# micro-circuit-ATMEGA32M1.net
KiCad netlist of a schematic drawn in Altium Designer
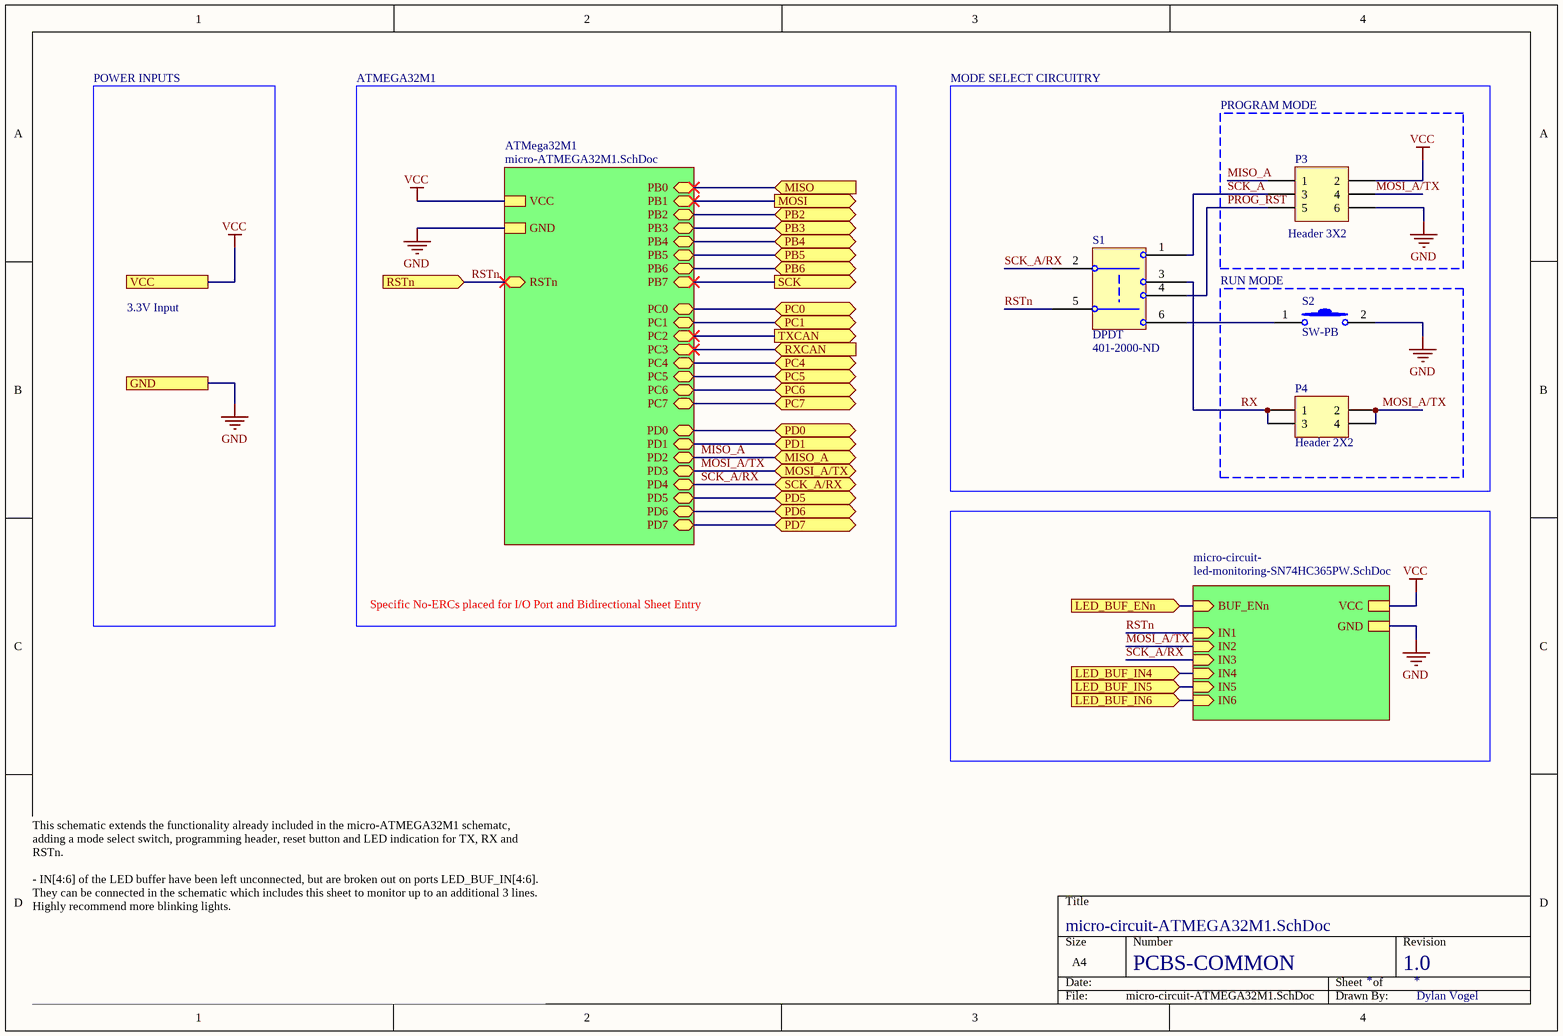
[diagram p0: micro-circuit-ATMEGA32M1.SchDoc]

(export (version "E")
  (design (tool "Eeschema 10.0.6"))
  (components
    (comp (ref "P3")
      (value "Header 3X2")
      (footprint "HDR2X3")
      (description "Header, 3-Pin, Dual row. Programming header")
      (fields (field (name "PUBLISHER") "Altium Limited"))
      (libsource (lib "Miscellaneous Connectors") (part "Header 3X2"))
    )
    (comp (ref "P4")
      (value "Header 2X2")
      (footprint "HDR2X2")
      (description "Header, 2-Pin, Dual row")
      (fields (field (name "PUBLISHER") "Altium Limited"))
      (libsource (lib "Miscellaneous Connectors") (part "Header 2X2"))
    )
    (comp (ref "S1")
      (value "DPDT")
      (footprint "JS202011AQN - Slide Switch")
      (description "DPDT Switch, customized for the pinout of the JS202011AQN switch.")
      (fields (field (name "SUPPLIER PART NUMBER 1") "401-2000-ND"))
      (libsource (lib "heron-general") (part "DPDT Switch"))
    )
    (comp (ref "S2")
      (value "SW-PB")
      (footprint "PTS830GM140 SMTR LFS - Pushbutton")
      (description "Schematic symbol for a generic 2-pin pushbutton, OFF-mom.")
      (libsource (lib "heron-general") (part "Pushbutton - Low Profile"))
    )
  )
  (nets
    (net (code "6") (name "/MISO_A") (class "Default")
      (node (ref "P3") (pin "1") (pinfunction "1_1") (pintype "passive"))
    )
    (net (code "8") (name "/MOSI_A{slash}TX") (class "Default")
      (node (ref "P3") (pin "4") (pinfunction "4_4") (pintype "passive"))
      (node (ref "P4") (pin "2") (pinfunction "2_2") (pintype "passive"))
      (node (ref "P4") (pin "4") (pinfunction "4_4") (pintype "passive"))
    )
    (net (code "25") (name "/PROG_RST") (class "Default")
      (node (ref "P3") (pin "5") (pinfunction "5_5") (pintype "passive"))
      (node (ref "S1") (pin "4") (pinfunction "POLE2A_4") (pintype "passive"))
    )
    (net (code "26") (name "/RSTn") (class "Default")
      (node (ref "S1") (pin "5") (pinfunction "POLE2_5") (pintype "passive+no_connect"))
    )
    (net (code "27") (name "/RX") (class "Default")
      (node (ref "P4") (pin "1") (pinfunction "1_1") (pintype "passive"))
      (node (ref "P4") (pin "3") (pinfunction "3_3") (pintype "passive"))
      (node (ref "S1") (pin "3") (pinfunction "POLE1B_3") (pintype "passive"))
    )
    (net (code "30") (name "/SCK_A") (class "Default")
      (node (ref "P3") (pin "3") (pinfunction "3_3") (pintype "passive"))
      (node (ref "S1") (pin "1") (pinfunction "POLE1A_1") (pintype "passive"))
    )
    (net (code "31") (name "/SCK_A{slash}RX") (class "Default")
      (node (ref "S1") (pin "2") (pinfunction "POLE1_2") (pintype "passive"))
    )
    (net (code "33") (name "GND") (class "Default")
      (node (ref "P3") (pin "6") (pinfunction "6_6") (pintype "passive"))
      (node (ref "S2") (pin "2") (pinfunction "2_2") (pintype "passive"))
    )
    (net (code "34") (name "Net-(S1-POLE2B)") (class "Default")
      (node (ref "S1") (pin "6") (pinfunction "POLE2B_6") (pintype "passive"))
      (node (ref "S2") (pin "1") (pinfunction "1_1") (pintype "passive"))
    )
    (net (code "35") (name "VCC") (class "Default")
      (node (ref "P3") (pin "2") (pinfunction "2_2") (pintype "passive"))
    )
  )
)
